# OpenMV-Shield.net
KiCad netlist of a schematic drawn in EAGLE
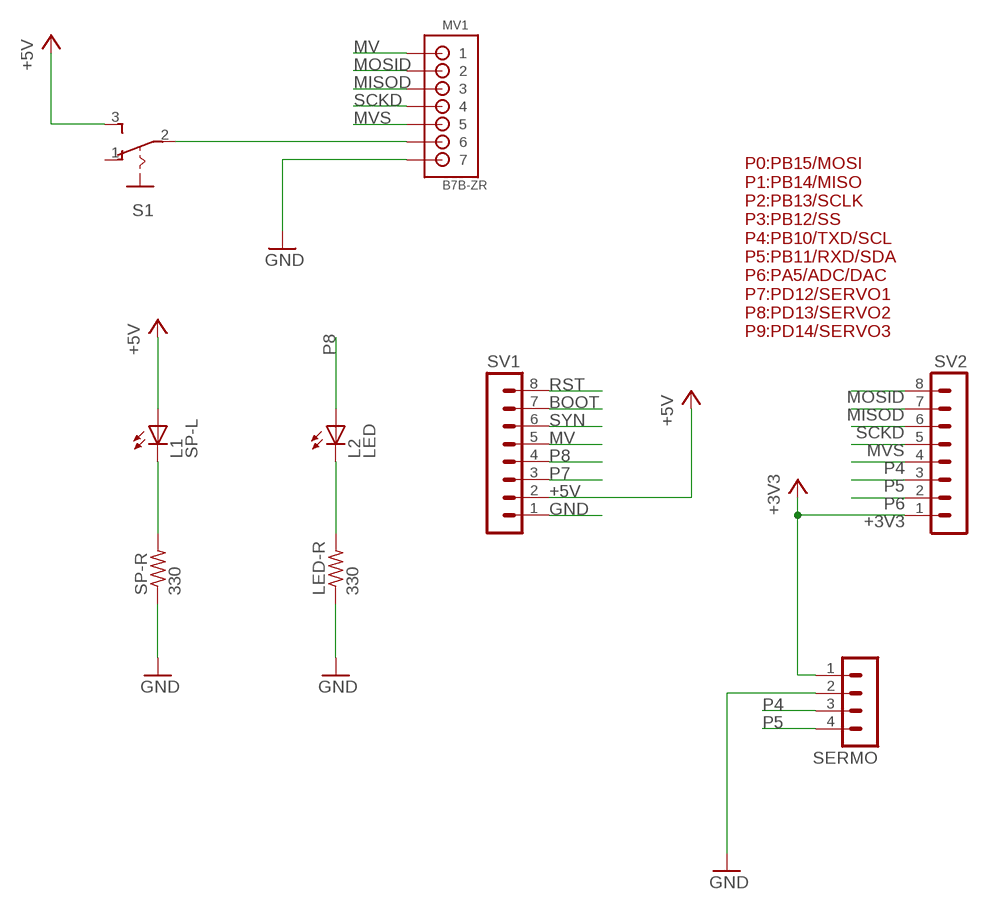
[diagram p0: schematic, sheet 1]

(export (version "E")
  (design (tool "Eeschema 10.0.6"))
  (components
    (comp (ref "L1")
      (value "SP-L")
      (footprint "eagle-import:CHIPLED_0805")
      (libsource (lib "eagle-import") (part "LEDCHIPLED_0805"))
    )
    (comp (ref "L2")
      (value "LED")
      (footprint "eagle-import:CHIPLED_0805")
      (libsource (lib "eagle-import") (part "LEDCHIPLED_0805"))
    )
    (comp (ref "LED-R")
      (value "330")
      (footprint "eagle-import:R0805")
      (libsource (lib "eagle-import") (part "R-US_R0805"))
    )
    (comp (ref "MV1")
      (value "B7B-ZR")
      (footprint "eagle-import:B7B-ZR")
      (libsource (lib "eagle-import") (part "B7B-ZR"))
    )
    (comp (ref "S1")
      (value "M251")
      (footprint "eagle-import:M251")
      (libsource (lib "eagle-import") (part "M251"))
    )
    (comp (ref "SERMO")
      (value "MA04-1")
      (footprint "eagle-import:MA04-1")
      (libsource (lib "eagle-import") (part "MA04-1"))
    )
    (comp (ref "SP-R")
      (value "330")
      (footprint "eagle-import:R0805")
      (libsource (lib "eagle-import") (part "R-US_R0805"))
    )
    (comp (ref "SV1")
      (value "MA08-1")
      (footprint "eagle-import:MA08-1")
      (libsource (lib "eagle-import") (part "MA08-1"))
    )
    (comp (ref "SV2")
      (value "MA08-1")
      (footprint "eagle-import:MA08-1")
      (libsource (lib "eagle-import") (part "MA08-1"))
    )
  )
  (nets
    (net (code "1") (name "+3V3") (class "Default")
      (node (ref "SERMO") (pin "1") (pinfunction "1_1") (pintype "passive"))
      (node (ref "SV2") (pin "1") (pinfunction "1_1") (pintype "passive"))
    )
    (net (code "2") (name "+5V") (class "Default")
      (node (ref "L1") (pin "A") (pinfunction "A_A") (pintype "passive"))
      (node (ref "S1") (pin "3") (pinfunction "S_3") (pintype "passive"))
      (node (ref "SV1") (pin "2") (pinfunction "2_2") (pintype "passive"))
    )
    (net (code "3") (name "/BOOT") (class "Default")
      (node (ref "SV1") (pin "7") (pinfunction "7_7") (pintype "passive"))
    )
    (net (code "4") (name "/MISOD") (class "Default")
      (node (ref "MV1") (pin "3") (pinfunction "3_3") (pintype "bidirectional"))
      (node (ref "SV2") (pin "7") (pinfunction "7_7") (pintype "passive"))
    )
    (net (code "5") (name "/MOSID") (class "Default")
      (node (ref "MV1") (pin "2") (pinfunction "2_2") (pintype "bidirectional"))
      (node (ref "SV2") (pin "8") (pinfunction "8_8") (pintype "passive"))
    )
    (net (code "6") (name "/MV") (class "Default")
      (node (ref "MV1") (pin "1") (pinfunction "1_1") (pintype "bidirectional"))
      (node (ref "SV1") (pin "5") (pinfunction "5_5") (pintype "passive"))
    )
    (net (code "7") (name "/MVS") (class "Default")
      (node (ref "MV1") (pin "5") (pinfunction "5_5") (pintype "bidirectional"))
      (node (ref "SV2") (pin "5") (pinfunction "5_5") (pintype "passive"))
    )
    (net (code "8") (name "/P4") (class "Default")
      (node (ref "SERMO") (pin "3") (pinfunction "3_3") (pintype "passive"))
      (node (ref "SV2") (pin "4") (pinfunction "4_4") (pintype "passive"))
    )
    (net (code "9") (name "/P5") (class "Default")
      (node (ref "SERMO") (pin "4") (pinfunction "4_4") (pintype "passive"))
      (node (ref "SV2") (pin "3") (pinfunction "3_3") (pintype "passive"))
    )
    (net (code "10") (name "/P6") (class "Default")
      (node (ref "SV2") (pin "2") (pinfunction "2_2") (pintype "passive"))
    )
    (net (code "11") (name "/P7") (class "Default")
      (node (ref "SV1") (pin "3") (pinfunction "3_3") (pintype "passive"))
    )
    (net (code "12") (name "/P8") (class "Default")
      (node (ref "L2") (pin "A") (pinfunction "A_A") (pintype "passive"))
      (node (ref "SV1") (pin "4") (pinfunction "4_4") (pintype "passive"))
    )
    (net (code "13") (name "/RST") (class "Default")
      (node (ref "SV1") (pin "8") (pinfunction "8_8") (pintype "passive"))
    )
    (net (code "14") (name "/SCKD") (class "Default")
      (node (ref "MV1") (pin "4") (pinfunction "4_4") (pintype "bidirectional"))
      (node (ref "SV2") (pin "6") (pinfunction "6_6") (pintype "passive"))
    )
    (net (code "15") (name "/SYN") (class "Default")
      (node (ref "SV1") (pin "6") (pinfunction "6_6") (pintype "passive"))
    )
    (net (code "16") (name "GND") (class "Default")
      (node (ref "LED-R") (pin "1") (pinfunction "1_1") (pintype "passive"))
      (node (ref "MV1") (pin "7") (pinfunction "7_7") (pintype "bidirectional"))
      (node (ref "SERMO") (pin "2") (pinfunction "2_2") (pintype "passive"))
      (node (ref "SP-R") (pin "1") (pinfunction "1_1") (pintype "passive"))
      (node (ref "SV1") (pin "1") (pinfunction "1_1") (pintype "passive"))
    )
    (net (code "17") (name "Net-(L1-PadC)") (class "Default")
      (node (ref "L1") (pin "C") (pinfunction "C_C") (pintype "passive"))
      (node (ref "SP-R") (pin "2") (pinfunction "2_2") (pintype "passive"))
    )
    (net (code "18") (name "Net-(L2-PadC)") (class "Default")
      (node (ref "L2") (pin "C") (pinfunction "C_C") (pintype "passive"))
      (node (ref "LED-R") (pin "2") (pinfunction "2_2") (pintype "passive"))
    )
    (net (code "19") (name "Net-(S1-P)") (class "Default")
      (node (ref "MV1") (pin "6") (pinfunction "6_6") (pintype "bidirectional"))
      (node (ref "S1") (pin "2") (pinfunction "P_2") (pintype "passive"))
    )
    (net (code "20") (name "unconnected-(S1-O-Pad1)") (class "Default")
      (node (ref "S1") (pin "1") (pinfunction "O_1") (pintype "passive"))
    )
  )
)
